# ONOFRE_ESTORES_COVERS_R1_0.net
KiCad netlist of a schematic drawn in EAGLE
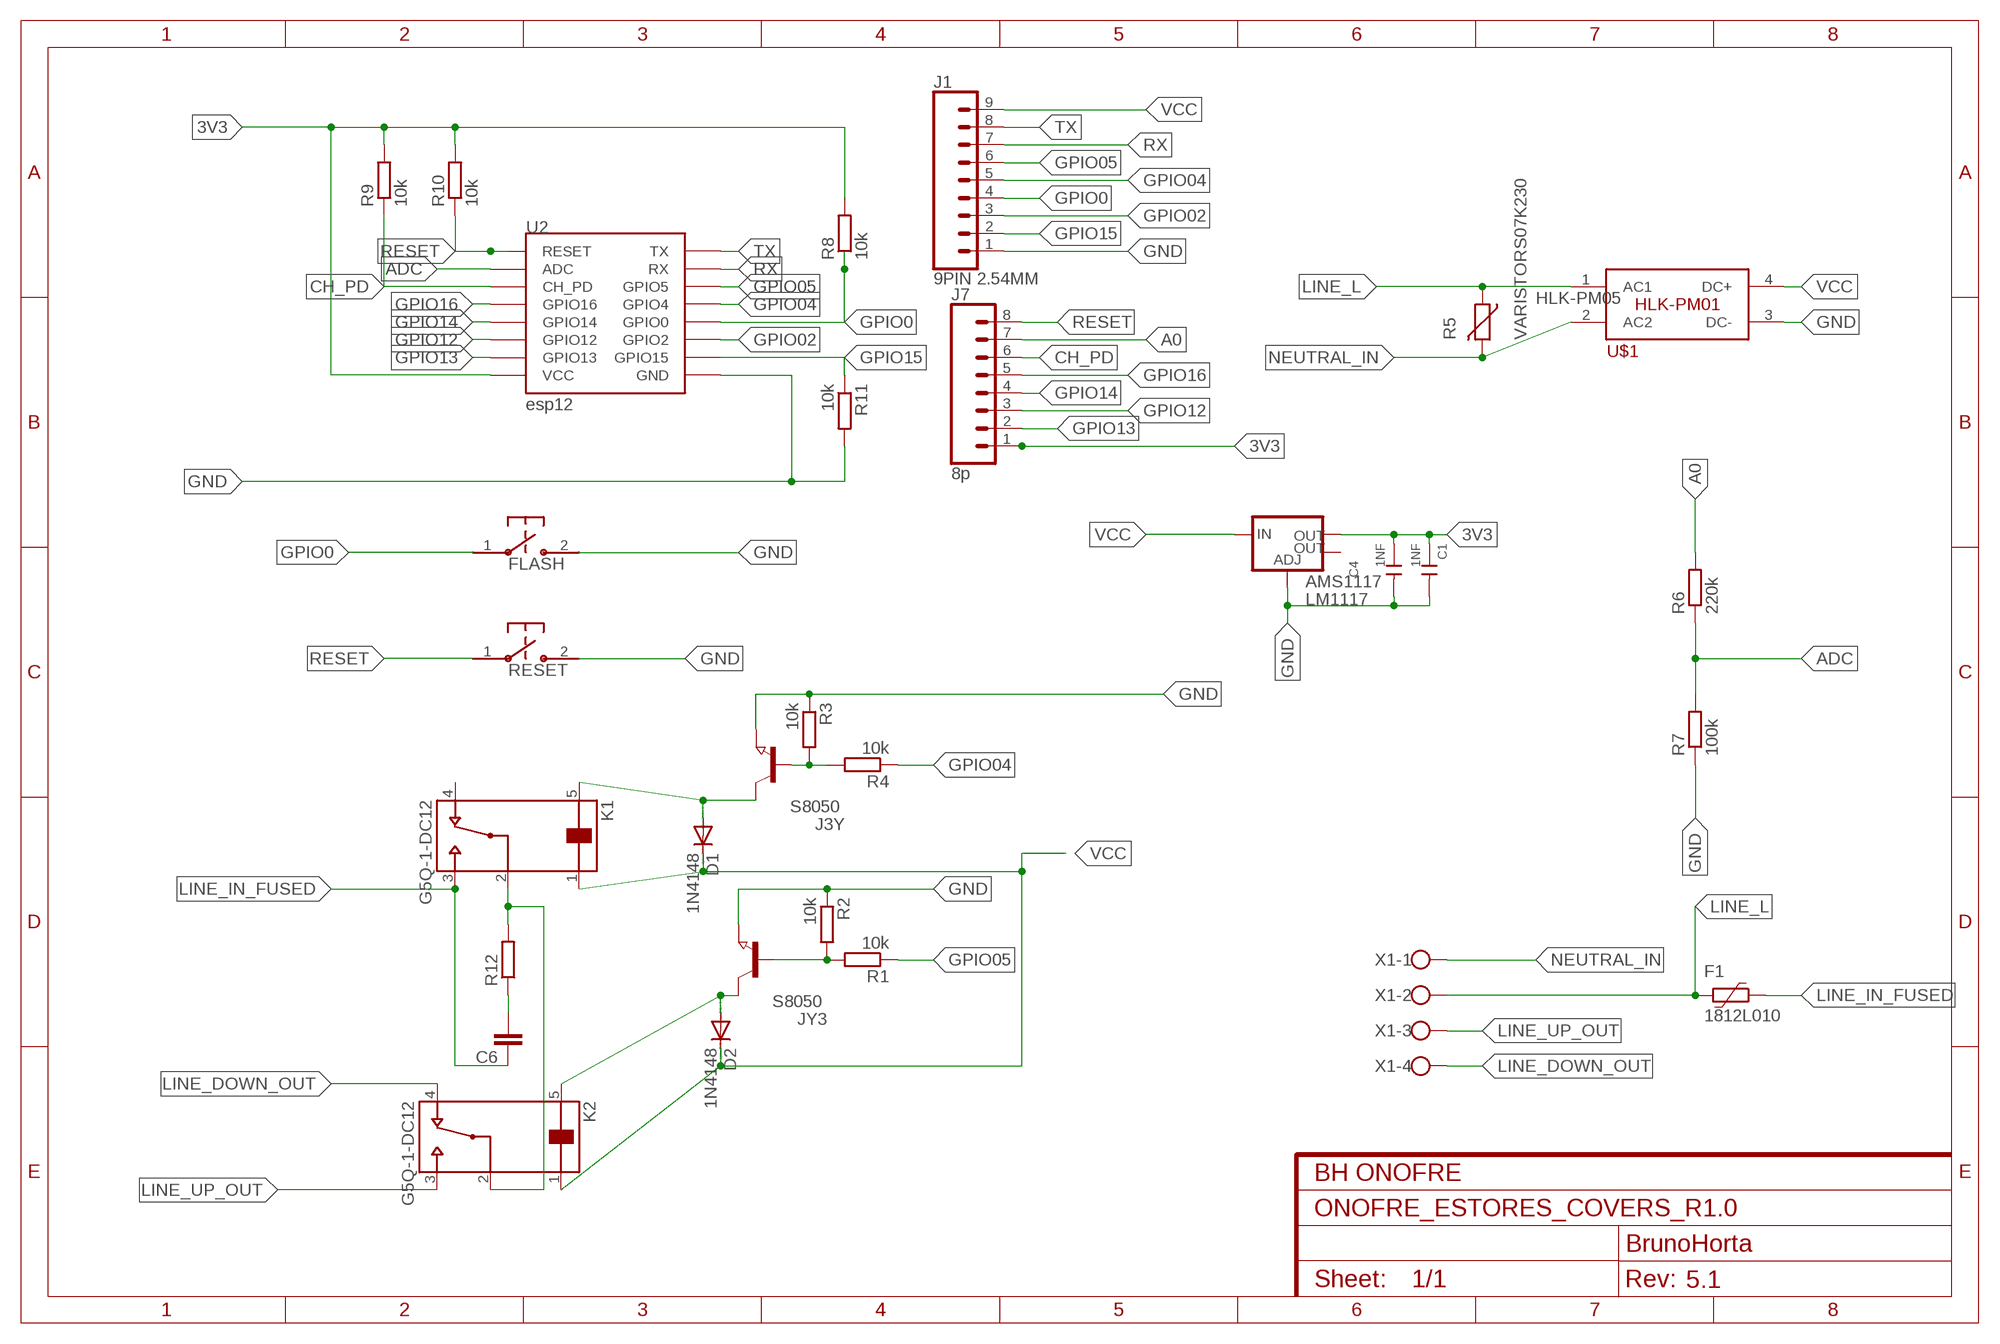
[diagram p0: schematic, sheet 1]

(export (version "E")
  (design (tool "Eeschema 10.0.6"))
  (components
    (comp (ref "AMS1117")
      (value "LM1117")
      (footprint "eagle-import:SOT223")
      (libsource (lib "eagle-import") (part "V_REG_LM1117SOT223"))
    )
    (comp (ref "C1")
      (value "1NF")
      (footprint "eagle-import:C1206")
      (fields (field (name "MPN") "CC1206KKX7RCBB102"))
      (libsource (lib "eagle-import") (part "CERAMIC-1NF-1KV-10%-X7R?(1206)"))
    )
    (comp (ref "C4")
      (value "1NF")
      (footprint "eagle-import:C1206")
      (fields (field (name "MPN") "CC1206KKX7RCBB102"))
      (libsource (lib "eagle-import") (part "CERAMIC-1NF-1KV-10%-X7R?(1206)"))
    )
    (comp (ref "C6")
      (value "C-EU102-043X133")
      (footprint "eagle-import:C102-043X133")
      (libsource (lib "eagle-import") (part "C-EU102-043X133"))
    )
    (comp (ref "D1")
      (value "1N4148")
      (footprint "eagle-import:SOD80C")
      (libsource (lib "eagle-import") (part "DIODE-SOD80C"))
    )
    (comp (ref "D2")
      (value "1N4148")
      (footprint "eagle-import:SOD80C")
      (libsource (lib "eagle-import") (part "DIODE-SOD80C"))
    )
    (comp (ref "F1")
      (value "1812L010")
      (footprint "eagle-import:1812L")
      (fields (field (name "MF") "Littelfuse"))
      (libsource (lib "eagle-import") (part "?1812L010"))
    )
    (comp (ref "FLASH")
      (value "B3U-1000P-2P-SMD")
      (footprint "eagle-import:B3U-1000P")
      (fields (field (name "MANUFACTURER") "Omron") (field (name "MPN") "B3U-1000P"))
      (libsource (lib "eagle-import") (part "B3U-1000P"))
    )
    (comp (ref "J1")
      (value "9PIN 2.54MM")
      (footprint "eagle-import:1X09")
      (libsource (lib "eagle-import") (part "CONN_09"))
    )
    (comp (ref "J3Y")
      (value "S8050")
      (footprint "eagle-import:SOT23")
      (libsource (lib "eagle-import") (part "NPN-TRANSISTOR_SOT23"))
    )
    (comp (ref "J7")
      (value "8p")
      (footprint "eagle-import:1X08")
      (libsource (lib "eagle-import") (part "CONN_08{dblquote}"))
    )
    (comp (ref "JY3")
      (value "S8050")
      (footprint "eagle-import:SOT23")
      (libsource (lib "eagle-import") (part "NPN-TRANSISTOR_SOT23"))
    )
    (comp (ref "K1")
      (value "G5Q-1-DC12")
      (footprint "eagle-import:RELAY_G5Q-1-DC12")
      (fields (field (name "MF") "Omron"))
      (libsource (lib "eagle-import") (part "G5Q-1-DC12"))
    )
    (comp (ref "K2")
      (value "G5Q-1-DC12")
      (footprint "eagle-import:RELAY_G5Q-1-DC12")
      (fields (field (name "MF") "Omron"))
      (libsource (lib "eagle-import") (part "G5Q-1-DC12"))
    )
    (comp (ref "R1")
      (value "10k")
      (footprint "eagle-import:R0603")
      (libsource (lib "eagle-import") (part "R-EU_R0603"))
    )
    (comp (ref "R2")
      (value "10k")
      (footprint "eagle-import:R0603")
      (libsource (lib "eagle-import") (part "R-EU_R0603"))
    )
    (comp (ref "R3")
      (value "10k")
      (footprint "eagle-import:R0603")
      (libsource (lib "eagle-import") (part "R-EU_R0603"))
    )
    (comp (ref "R4")
      (value "10k")
      (footprint "eagle-import:R0603")
      (libsource (lib "eagle-import") (part "R-EU_R0603"))
    )
    (comp (ref "R5")
      (value "VARISTORS07K230")
      (footprint "eagle-import:S07K230")
      (libsource (lib "eagle-import") (part "VARISTORS07K230"))
    )
    (comp (ref "R6")
      (value "220k")
      (footprint "eagle-import:R0603")
      (libsource (lib "eagle-import") (part "R-EU_R0603"))
    )
    (comp (ref "R7")
      (value "100k")
      (footprint "eagle-import:R0603")
      (libsource (lib "eagle-import") (part "R-EU_R0603"))
    )
    (comp (ref "R8")
      (value "10k")
      (footprint "eagle-import:R0603")
      (libsource (lib "eagle-import") (part "R-EU_R0603"))
    )
    (comp (ref "R9")
      (value "10k")
      (footprint "eagle-import:R0603")
      (libsource (lib "eagle-import") (part "R-EU_R0603"))
    )
    (comp (ref "R10")
      (value "10k")
      (footprint "eagle-import:R0603")
      (libsource (lib "eagle-import") (part "R-EU_R0603"))
    )
    (comp (ref "R11")
      (value "10k")
      (footprint "eagle-import:R0603")
      (libsource (lib "eagle-import") (part "R-EU_R0603"))
    )
    (comp (ref "R12")
      (value "R-EU_R2512")
      (footprint "eagle-import:R2512")
      (libsource (lib "eagle-import") (part "R-EU_R2512"))
    )
    (comp (ref "RESET")
      (value "B3U-1000P-2P-SMD")
      (footprint "eagle-import:B3U-1000P")
      (fields (field (name "MANUFACTURER") "Omron") (field (name "MPN") "B3U-1000P"))
      (libsource (lib "eagle-import") (part "B3U-1000P"))
    )
    (comp (ref "U$1")
      (value "HLK-PM01")
      (footprint "eagle-import:HLK-PM01")
      (fields (field (name "MF") "Hi-link") (field (name "MP") "hlk-pm01"))
      (libsource (lib "eagle-import") (part "HLK-PM01"))
    )
    (comp (ref "U2")
      (value "esp12")
      (footprint "eagle-import:ESP12-SMD")
      (libsource (lib "eagle-import") (part "ESP12SMD"))
    )
    (comp (ref "X1")
      (value "W237-4")
      (footprint "eagle-import:W237-4")
      (libsource (lib "eagle-import") (part "W237-4"))
    )
  )
  (nets
    (net (code "1") (name "3V3") (class "Default")
      (node (ref "AMS1117") (pin "2") (pinfunction "OUT_2") (pintype "output"))
      (node (ref "C1") (pin "1") (pinfunction "1_1") (pintype "passive"))
      (node (ref "C4") (pin "1") (pinfunction "1_1") (pintype "passive"))
      (node (ref "J7") (pin "1") (pinfunction "1_1") (pintype "passive"))
      (node (ref "R10") (pin "2") (pinfunction "2_2") (pintype "passive"))
      (node (ref "R8") (pin "2") (pinfunction "2_2") (pintype "passive"))
      (node (ref "R9") (pin "2") (pinfunction "2_2") (pintype "passive"))
      (node (ref "U2") (pin "VCC") (pinfunction "VCC_VCC") (pintype "bidirectional"))
    )
    (net (code "2") (name "A0") (class "Default")
      (node (ref "J7") (pin "7") (pinfunction "7_7") (pintype "passive"))
      (node (ref "R6") (pin "2") (pinfunction "2_2") (pintype "passive"))
    )
    (net (code "3") (name "ADC") (class "Default")
      (node (ref "R6") (pin "1") (pinfunction "1_1") (pintype "passive"))
      (node (ref "R7") (pin "2") (pinfunction "2_2") (pintype "passive"))
      (node (ref "U2") (pin "ADC") (pinfunction "ADC_ADC") (pintype "bidirectional"))
    )
    (net (code "4") (name "CH_PD") (class "Default")
      (node (ref "J7") (pin "6") (pinfunction "6_6") (pintype "passive"))
      (node (ref "R9") (pin "1") (pinfunction "1_1") (pintype "passive"))
      (node (ref "U2") (pin "CH_PD") (pinfunction "CH_PD_CH_PD") (pintype "bidirectional"))
    )
    (net (code "5") (name "GND") (class "Default")
      (node (ref "AMS1117") (pin "1") (pinfunction "ADJ_1") (pintype "input"))
      (node (ref "C1") (pin "2") (pinfunction "2_2") (pintype "passive"))
      (node (ref "C4") (pin "2") (pinfunction "2_2") (pintype "passive"))
      (node (ref "FLASH") (pin "2") (pinfunction "P$2_2") (pintype "passive"))
      (node (ref "J1") (pin "1") (pinfunction "1_1") (pintype "passive"))
      (node (ref "J3Y") (pin "2") (pinfunction "E_2") (pintype "passive"))
      (node (ref "JY3") (pin "2") (pinfunction "E_2") (pintype "passive"))
      (node (ref "R11") (pin "2") (pinfunction "2_2") (pintype "passive"))
      (node (ref "R2") (pin "1") (pinfunction "1_1") (pintype "passive"))
      (node (ref "R3") (pin "1") (pinfunction "1_1") (pintype "passive"))
      (node (ref "R7") (pin "1") (pinfunction "1_1") (pintype "passive"))
      (node (ref "RESET") (pin "2") (pinfunction "P$2_2") (pintype "passive"))
      (node (ref "U$1") (pin "3") (pinfunction "DC-_3") (pintype "power_in"))
      (node (ref "U2") (pin "GND") (pinfunction "GND_GND") (pintype "bidirectional"))
    )
    (net (code "6") (name "GPIO0") (class "Default")
      (node (ref "FLASH") (pin "1") (pinfunction "P$1_1") (pintype "passive"))
      (node (ref "J1") (pin "4") (pinfunction "4_4") (pintype "passive"))
      (node (ref "R8") (pin "1") (pinfunction "1_1") (pintype "passive"))
      (node (ref "U2") (pin "GPIO0") (pinfunction "GPIO0_GPIO0") (pintype "bidirectional"))
    )
    (net (code "7") (name "GPIO02") (class "Default")
      (node (ref "J1") (pin "3") (pinfunction "3_3") (pintype "passive"))
      (node (ref "U2") (pin "GPIO2") (pinfunction "GPIO2_GPIO2") (pintype "bidirectional"))
    )
    (net (code "8") (name "GPIO04") (class "Default")
      (node (ref "J1") (pin "5") (pinfunction "5_5") (pintype "passive"))
      (node (ref "R4") (pin "1") (pinfunction "1_1") (pintype "passive"))
      (node (ref "U2") (pin "GPIO4") (pinfunction "GPIO4_GPIO4") (pintype "bidirectional"))
    )
    (net (code "9") (name "GPIO05") (class "Default")
      (node (ref "J1") (pin "6") (pinfunction "6_6") (pintype "passive"))
      (node (ref "R1") (pin "1") (pinfunction "1_1") (pintype "passive"))
      (node (ref "U2") (pin "GPIO5") (pinfunction "GPIO5_GPIO5") (pintype "bidirectional"))
    )
    (net (code "10") (name "GPIO12") (class "Default")
      (node (ref "J7") (pin "3") (pinfunction "3_3") (pintype "passive"))
      (node (ref "U2") (pin "GPIO12") (pinfunction "GPIO12_GPIO12") (pintype "bidirectional"))
    )
    (net (code "11") (name "GPIO13") (class "Default")
      (node (ref "J7") (pin "2") (pinfunction "2_2") (pintype "passive"))
      (node (ref "U2") (pin "GPIO13") (pinfunction "GPIO13_GPIO13") (pintype "bidirectional"))
    )
    (net (code "12") (name "GPIO14") (class "Default")
      (node (ref "J7") (pin "4") (pinfunction "4_4") (pintype "passive"))
      (node (ref "U2") (pin "GPIO14") (pinfunction "GPIO14_GPIO14") (pintype "bidirectional"))
    )
    (net (code "13") (name "GPIO15") (class "Default")
      (node (ref "J1") (pin "2") (pinfunction "2_2") (pintype "passive"))
      (node (ref "R11") (pin "1") (pinfunction "1_1") (pintype "passive"))
      (node (ref "U2") (pin "GPIO15") (pinfunction "GPIO15_GPIO15") (pintype "bidirectional"))
    )
    (net (code "14") (name "GPIO16") (class "Default")
      (node (ref "J7") (pin "5") (pinfunction "5_5") (pintype "passive"))
      (node (ref "U2") (pin "GPIO16") (pinfunction "GPIO16_GPIO16") (pintype "bidirectional"))
    )
    (net (code "15") (name "LINE_DOWN_OUT") (class "Default")
      (node (ref "K2") (pin "4") (pinfunction "4_4") (pintype "passive"))
      (node (ref "X1") (pin "4") (pinfunction "KL_4") (pintype "passive"))
    )
    (net (code "16") (name "LINE_IN_FUSED") (class "Default")
      (node (ref "C6") (pin "1") (pinfunction "1_1") (pintype "passive"))
      (node (ref "F1") (pin "1") (pinfunction "1_1") (pintype "passive"))
      (node (ref "K1") (pin "3") (pinfunction "3_3") (pintype "passive"))
    )
    (net (code "17") (name "LINE_L") (class "Default")
      (node (ref "F1") (pin "2") (pinfunction "2_2") (pintype "passive"))
      (node (ref "R5") (pin "1") (pinfunction "1_1") (pintype "passive"))
      (node (ref "U$1") (pin "1") (pinfunction "AC1_1") (pintype "power_in"))
      (node (ref "X1") (pin "2") (pinfunction "KL_2") (pintype "passive"))
    )
    (net (code "18") (name "LINE_UP_OUT") (class "Default")
      (node (ref "K2") (pin "3") (pinfunction "3_3") (pintype "passive"))
      (node (ref "X1") (pin "3") (pinfunction "KL_3") (pintype "passive"))
    )
    (net (code "19") (name "NEUTRAL_IN") (class "Default")
      (node (ref "R5") (pin "2") (pinfunction "2_2") (pintype "passive"))
      (node (ref "U$1") (pin "2") (pinfunction "AC2_2") (pintype "power_in"))
      (node (ref "X1") (pin "1") (pinfunction "KL_1") (pintype "passive"))
    )
    (net (code "20") (name "Net-(C6-Pad2)") (class "Default")
      (node (ref "C6") (pin "2") (pinfunction "2_2") (pintype "passive"))
      (node (ref "R12") (pin "1") (pinfunction "1_1") (pintype "passive"))
    )
    (net (code "21") (name "Net-(J3Y-B)") (class "Default")
      (node (ref "J3Y") (pin "1") (pinfunction "B_1") (pintype "passive"))
      (node (ref "R3") (pin "2") (pinfunction "2_2") (pintype "passive"))
      (node (ref "R4") (pin "2") (pinfunction "2_2") (pintype "passive"))
    )
    (net (code "22") (name "Net-(J3Y-C)") (class "Default")
      (node (ref "D1") (pin "A") (pinfunction "A_A") (pintype "passive"))
      (node (ref "J3Y") (pin "3") (pinfunction "C_3") (pintype "passive"))
      (node (ref "K1") (pin "5") (pinfunction "5_5") (pintype "passive"))
    )
    (net (code "23") (name "Net-(JY3-B)") (class "Default")
      (node (ref "JY3") (pin "1") (pinfunction "B_1") (pintype "passive"))
      (node (ref "R1") (pin "2") (pinfunction "2_2") (pintype "passive"))
      (node (ref "R2") (pin "2") (pinfunction "2_2") (pintype "passive"))
    )
    (net (code "24") (name "Net-(JY3-C)") (class "Default")
      (node (ref "D2") (pin "A") (pinfunction "A_A") (pintype "passive"))
      (node (ref "JY3") (pin "3") (pinfunction "C_3") (pintype "passive"))
      (node (ref "K2") (pin "5") (pinfunction "5_5") (pintype "passive"))
    )
    (net (code "25") (name "Net-(K1-Pad2)") (class "Default")
      (node (ref "K1") (pin "2") (pinfunction "2_2") (pintype "passive"))
      (node (ref "K2") (pin "2") (pinfunction "2_2") (pintype "passive"))
      (node (ref "R12") (pin "2") (pinfunction "2_2") (pintype "passive"))
    )
    (net (code "26") (name "RESET") (class "Default")
      (node (ref "J7") (pin "8") (pinfunction "8_8") (pintype "passive"))
      (node (ref "R10") (pin "1") (pinfunction "1_1") (pintype "passive"))
      (node (ref "RESET") (pin "1") (pinfunction "P$1_1") (pintype "passive"))
      (node (ref "U2") (pin "RESET") (pinfunction "RESET_RESET") (pintype "bidirectional"))
    )
    (net (code "27") (name "RX") (class "Default")
      (node (ref "J1") (pin "7") (pinfunction "7_7") (pintype "passive"))
      (node (ref "U2") (pin "RXD0") (pinfunction "RX_RXD0") (pintype "bidirectional"))
    )
    (net (code "28") (name "TX") (class "Default")
      (node (ref "J1") (pin "8") (pinfunction "8_8") (pintype "passive"))
      (node (ref "U2") (pin "TXD0") (pinfunction "TX_TXD0") (pintype "bidirectional"))
    )
    (net (code "29") (name "VCC") (class "Default")
      (node (ref "AMS1117") (pin "3") (pinfunction "IN_3") (pintype "input"))
      (node (ref "D1") (pin "C") (pinfunction "C_C") (pintype "passive"))
      (node (ref "D2") (pin "C") (pinfunction "C_C") (pintype "passive"))
      (node (ref "J1") (pin "9") (pinfunction "9_9") (pintype "passive"))
      (node (ref "K1") (pin "1") (pinfunction "1_1") (pintype "passive"))
      (node (ref "K2") (pin "1") (pinfunction "1_1") (pintype "passive"))
      (node (ref "U$1") (pin "4") (pinfunction "DC+_4") (pintype "power_in"))
    )
    (net (code "30") (name "unconnected-(AMS1117-OUT-Pad4)") (class "Default")
      (node (ref "AMS1117") (pin "4") (pinfunction "OUT_4") (pintype "output"))
    )
    (net (code "31") (name "unconnected-(K1-Pad4)") (class "Default")
      (node (ref "K1") (pin "4") (pinfunction "4_4") (pintype "passive"))
    )
  )
)
